# untitled.net
KiCad netlist of a schematic drawn in EAGLE
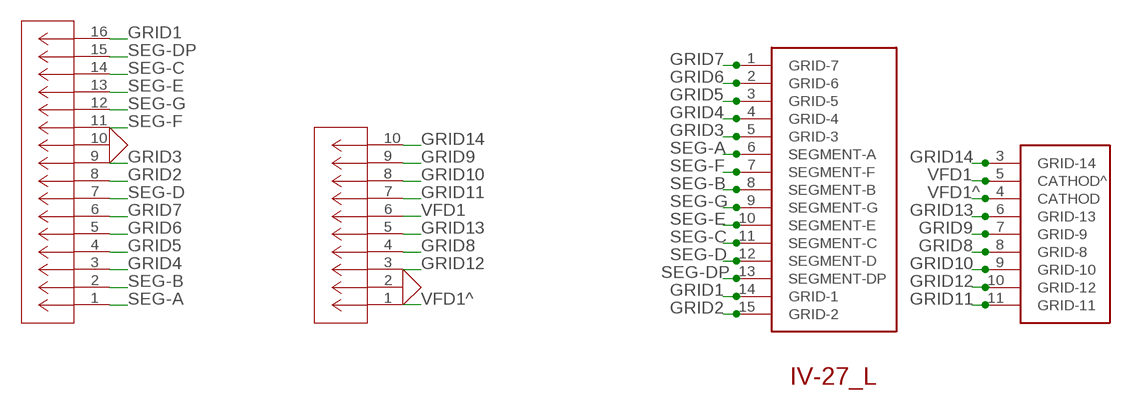
[diagram p0: schematic, sheet 1]

(export (version "E")
  (design (tool "Eeschema 10.0.6"))
  (components
    (comp (ref "IV-27_L")
      (value "8-215079-6")
      (footprint "eagle-import:CONN16_8-215079-6")
      (fields (field (name "MANUFACTURER_PART_NUMBER") "82150796"))
      (libsource (lib "eagle-import") (part "8-215079-6"))
    )
    (comp (ref "IV-27_R")
      (value "8-215079-0")
      (footprint "eagle-import:CONN10_8-215079-0")
      (fields (field (name "MANUFACTURER_PART_NUMBER") "82150790"))
      (libsource (lib "eagle-import") (part "8-215079-0"))
    )
    (comp (ref "U$1")
      (value "IV-27_L")
      (footprint "eagle-import:IV-27_L")
      (libsource (lib "eagle-import") (part "IV-27_L"))
    )
    (comp (ref "U$2")
      (value "IV-27_R")
      (footprint "eagle-import:IV-27_R")
      (libsource (lib "eagle-import") (part "IV-27_R"))
    )
  )
  (nets
    (net (code "1") (name "/GRID1") (class "Default")
      (node (ref "IV-27_L") (pin "16") (pinfunction "16_16") (pintype "passive"))
      (node (ref "U$1") (pin "14") (pinfunction "GRID-1_14") (pintype "bidirectional"))
    )
    (net (code "2") (name "/GRID2") (class "Default")
      (node (ref "IV-27_L") (pin "8") (pinfunction "8_8") (pintype "passive"))
      (node (ref "U$1") (pin "15") (pinfunction "GRID-2_15") (pintype "bidirectional"))
    )
    (net (code "3") (name "/GRID3") (class "Default")
      (node (ref "IV-27_L") (pin "9") (pinfunction "9_9") (pintype "passive"))
      (node (ref "U$1") (pin "5") (pinfunction "GRID-3_5") (pintype "bidirectional"))
    )
    (net (code "4") (name "/GRID4") (class "Default")
      (node (ref "IV-27_L") (pin "3") (pinfunction "3_3") (pintype "passive"))
      (node (ref "U$1") (pin "4") (pinfunction "GRID-4_4") (pintype "bidirectional"))
    )
    (net (code "5") (name "/GRID5") (class "Default")
      (node (ref "IV-27_L") (pin "4") (pinfunction "4_4") (pintype "passive"))
      (node (ref "U$1") (pin "3") (pinfunction "GRID-5_3") (pintype "bidirectional"))
    )
    (net (code "6") (name "/GRID6") (class "Default")
      (node (ref "IV-27_L") (pin "5") (pinfunction "5_5") (pintype "passive"))
      (node (ref "U$1") (pin "2") (pinfunction "GRID-6_2") (pintype "bidirectional"))
    )
    (net (code "7") (name "/GRID7") (class "Default")
      (node (ref "IV-27_L") (pin "6") (pinfunction "6_6") (pintype "passive"))
      (node (ref "U$1") (pin "1") (pinfunction "GRID-7_1") (pintype "bidirectional"))
    )
    (net (code "8") (name "/GRID8") (class "Default")
      (node (ref "IV-27_R") (pin "4") (pinfunction "4_4") (pintype "passive"))
      (node (ref "U$2") (pin "8") (pinfunction "GRID-8_8") (pintype "bidirectional"))
    )
    (net (code "9") (name "/GRID9") (class "Default")
      (node (ref "IV-27_R") (pin "9") (pinfunction "9_9") (pintype "passive"))
      (node (ref "U$2") (pin "7") (pinfunction "GRID-9_7") (pintype "bidirectional"))
    )
    (net (code "10") (name "/GRID10") (class "Default")
      (node (ref "IV-27_R") (pin "8") (pinfunction "8_8") (pintype "passive"))
      (node (ref "U$2") (pin "9") (pinfunction "GRID-10_9") (pintype "bidirectional"))
    )
    (net (code "11") (name "/GRID11") (class "Default")
      (node (ref "IV-27_R") (pin "7") (pinfunction "7_7") (pintype "passive"))
      (node (ref "U$2") (pin "11") (pinfunction "GRID-11_11") (pintype "bidirectional"))
    )
    (net (code "12") (name "/GRID12") (class "Default")
      (node (ref "IV-27_R") (pin "3") (pinfunction "3_3") (pintype "passive"))
      (node (ref "U$2") (pin "10") (pinfunction "GRID-12_10") (pintype "bidirectional"))
    )
    (net (code "13") (name "/GRID13") (class "Default")
      (node (ref "IV-27_R") (pin "5") (pinfunction "5_5") (pintype "passive"))
      (node (ref "U$2") (pin "6") (pinfunction "GRID-13_6") (pintype "bidirectional"))
    )
    (net (code "14") (name "/GRID14") (class "Default")
      (node (ref "IV-27_R") (pin "10") (pinfunction "10_10") (pintype "passive"))
      (node (ref "U$2") (pin "3") (pinfunction "GRID-14_3") (pintype "bidirectional"))
    )
    (net (code "15") (name "/SEG-A") (class "Default")
      (node (ref "IV-27_L") (pin "1") (pinfunction "1_1") (pintype "passive"))
      (node (ref "U$1") (pin "6") (pinfunction "SEGMENT-A_6") (pintype "bidirectional"))
    )
    (net (code "16") (name "/SEG-B") (class "Default")
      (node (ref "IV-27_L") (pin "2") (pinfunction "2_2") (pintype "passive"))
      (node (ref "U$1") (pin "8") (pinfunction "SEGMENT-B_8") (pintype "bidirectional"))
    )
    (net (code "17") (name "/SEG-C") (class "Default")
      (node (ref "IV-27_L") (pin "14") (pinfunction "14_14") (pintype "passive"))
      (node (ref "U$1") (pin "11") (pinfunction "SEGMENT-C_11") (pintype "bidirectional"))
    )
    (net (code "18") (name "/SEG-D") (class "Default")
      (node (ref "IV-27_L") (pin "7") (pinfunction "7_7") (pintype "passive"))
      (node (ref "U$1") (pin "12") (pinfunction "SEGMENT-D_12") (pintype "bidirectional"))
    )
    (net (code "19") (name "/SEG-DP") (class "Default")
      (node (ref "IV-27_L") (pin "15") (pinfunction "15_15") (pintype "passive"))
      (node (ref "U$1") (pin "13") (pinfunction "SEGMENT-DP_13") (pintype "bidirectional"))
    )
    (net (code "20") (name "/SEG-E") (class "Default")
      (node (ref "IV-27_L") (pin "13") (pinfunction "13_13") (pintype "passive"))
      (node (ref "U$1") (pin "10") (pinfunction "SEGMENT-E_10") (pintype "bidirectional"))
    )
    (net (code "21") (name "/SEG-F") (class "Default")
      (node (ref "IV-27_L") (pin "11") (pinfunction "11_11") (pintype "passive"))
      (node (ref "U$1") (pin "7") (pinfunction "SEGMENT-F_7") (pintype "bidirectional"))
    )
    (net (code "22") (name "/SEG-G") (class "Default")
      (node (ref "IV-27_L") (pin "12") (pinfunction "12_12") (pintype "passive"))
      (node (ref "U$1") (pin "9") (pinfunction "SEGMENT-G_9") (pintype "bidirectional"))
    )
    (net (code "23") (name "/VFD1") (class "Default")
      (node (ref "IV-27_R") (pin "6") (pinfunction "6_6") (pintype "passive"))
      (node (ref "U$2") (pin "5") (pinfunction "CATHOD^_5") (pintype "bidirectional"))
    )
    (net (code "24") (name "/VFD1^") (class "Default")
      (node (ref "IV-27_R") (pin "1") (pinfunction "1_1") (pintype "passive"))
      (node (ref "U$2") (pin "4") (pinfunction "CATHOD_4") (pintype "bidirectional"))
    )
    (net (code "25") (name "GND") (class "Default")
      (node (ref "IV-27_L") (pin "10") (pinfunction "10_10") (pintype "passive"))
      (node (ref "IV-27_R") (pin "2") (pinfunction "2_2") (pintype "passive"))
    )
  )
)
